# Levels.net
KiCad netlist of a schematic drawn in Altium Designer
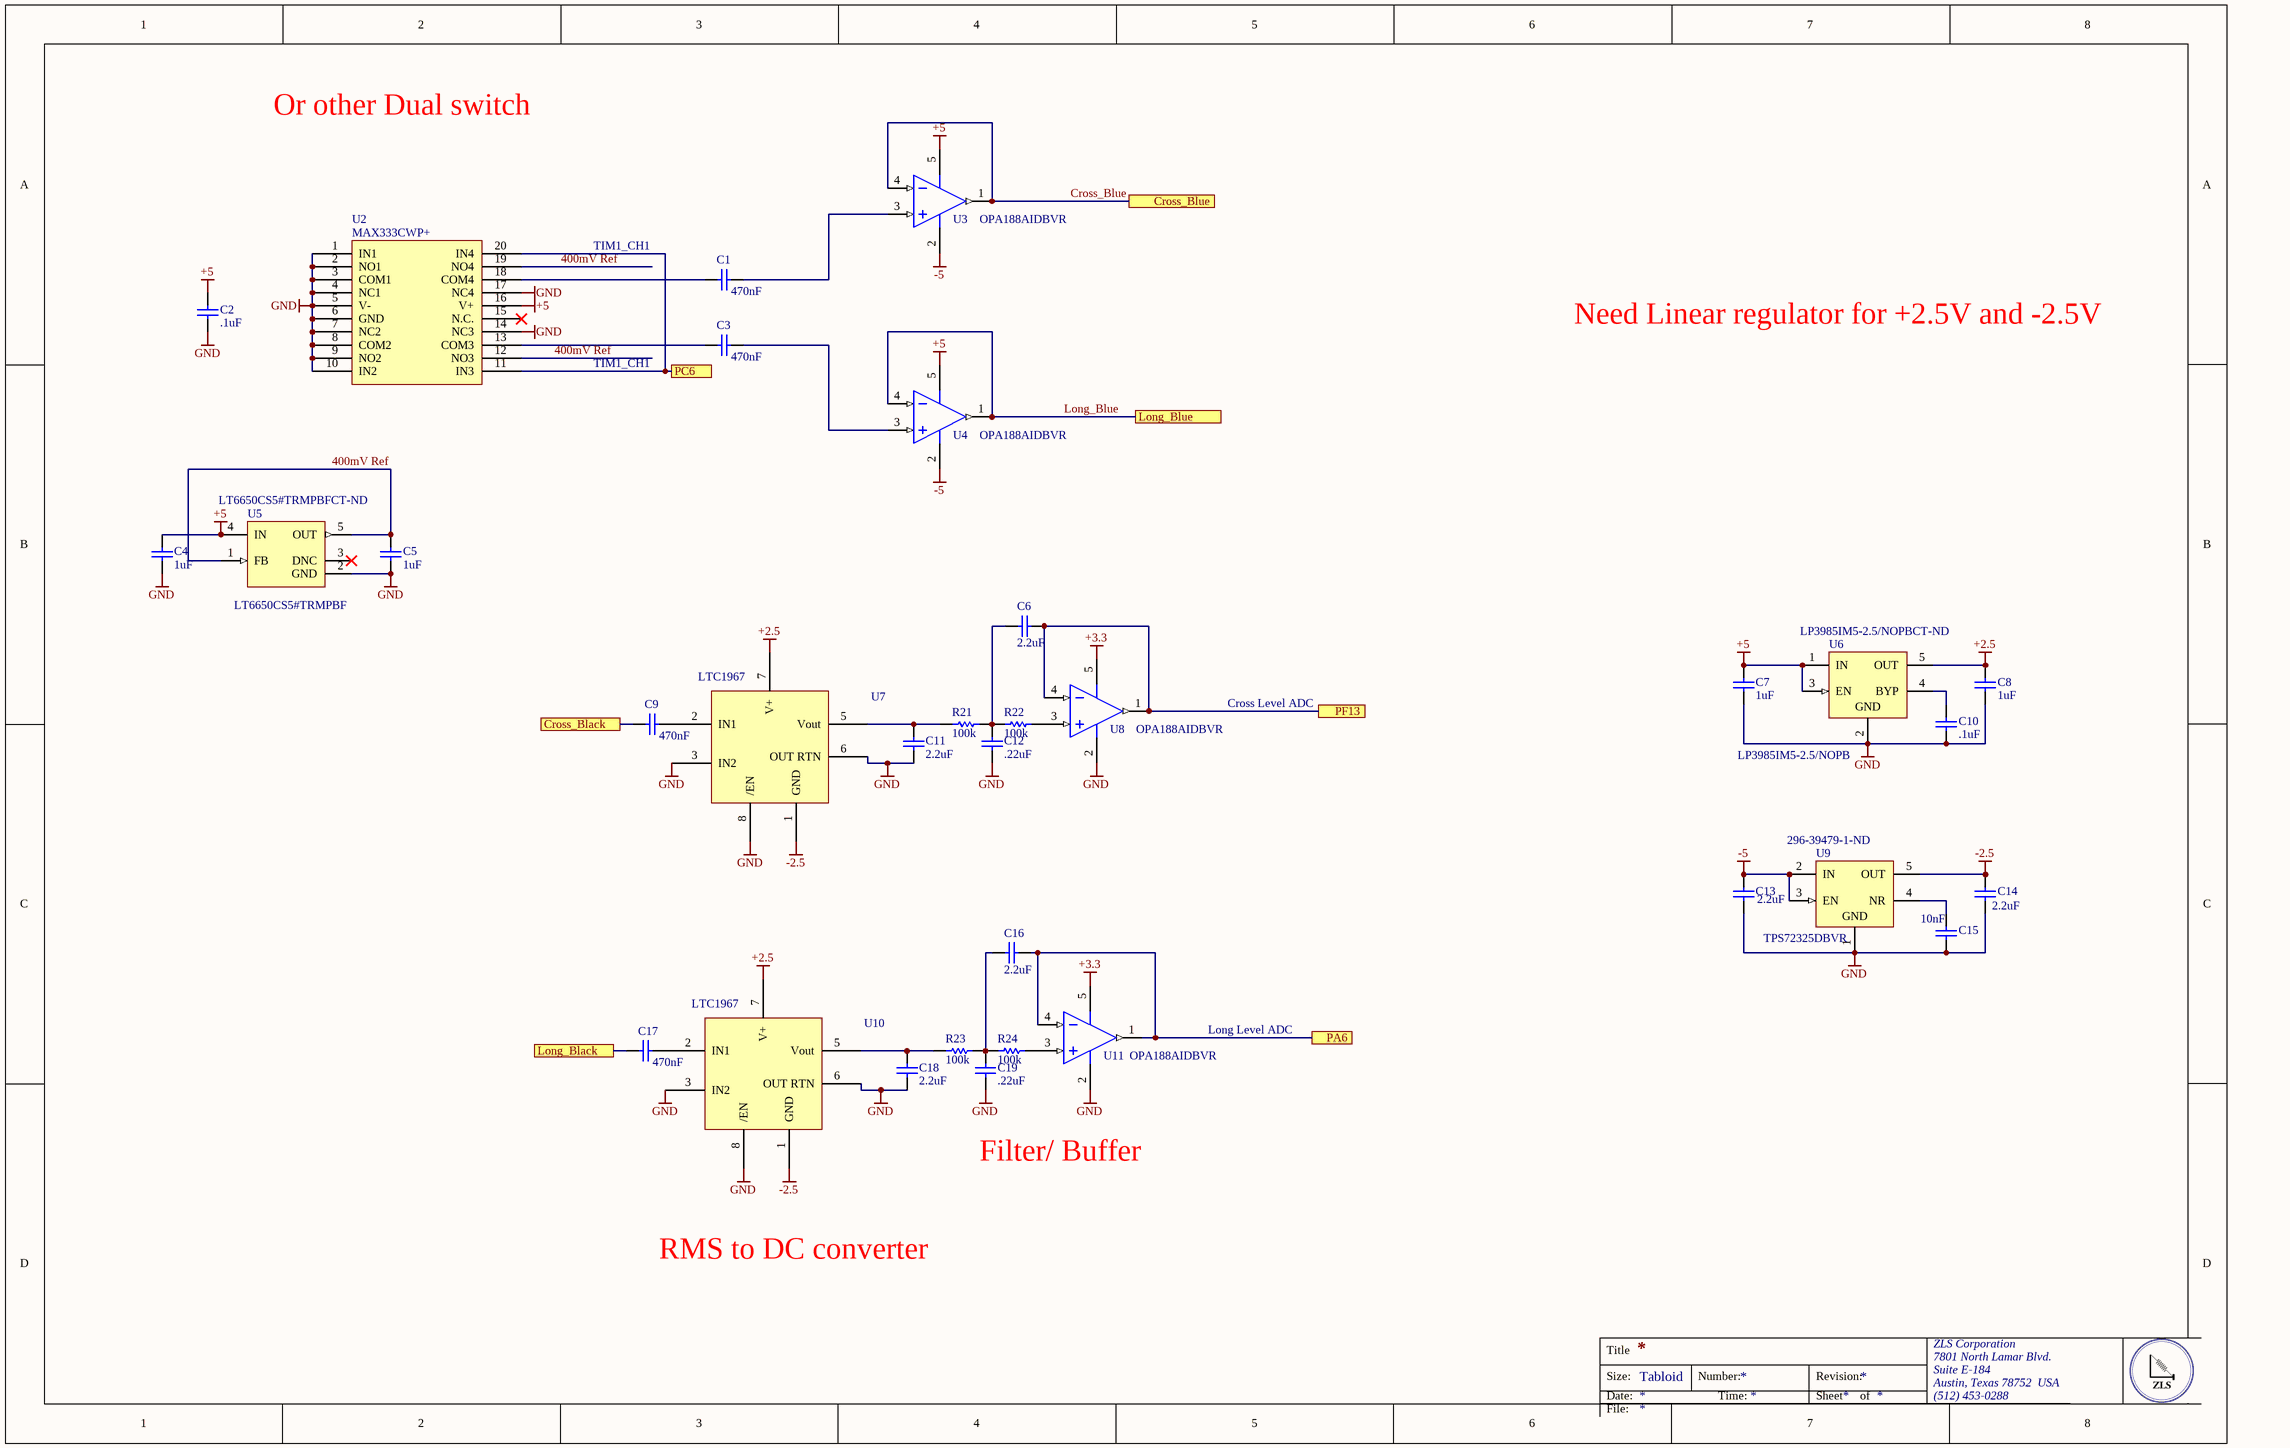
[diagram p0: Levels.SchDoc]

(export (version "E")
  (design (tool "Eeschema 10.0.6"))
  (components
    (comp (ref "C1")
      (value "470nF")
      (footprint "CAPC0805(2012)75_L")
      (description "CAP 150pF 16V ±10% 0805 (2012 Metric) Thickness 0.75mm SMD")
      (fields (field (name "TOLERANCE") "Â±10%"))
      (libsource (lib "Altium Content Vault") (part "CMP-1036-02117-1"))
    )
    (comp (ref "C2")
      (value ".1uF")
      (footprint "CAPC0805(2012)75_L")
      (description "CAP 150pF 16V ±10% 0805 (2012 Metric) Thickness 0.75mm SMD")
      (fields (field (name "TOLERANCE") "Â±10%"))
      (libsource (lib "Altium Content Vault") (part "CMP-1036-02117-1"))
    )
    (comp (ref "C3")
      (value "470nF")
      (footprint "CAPC0805(2012)75_L")
      (description "CAP 150pF 16V ±10% 0805 (2012 Metric) Thickness 0.75mm SMD")
      (fields (field (name "TOLERANCE") "Â±10%"))
      (libsource (lib "Altium Content Vault") (part "CMP-1036-02117-1"))
    )
    (comp (ref "C4")
      (value "08053C105JAT2A")
      (footprint "CAPC0805(2012)145_N")
      (description "1µF ±5% 25V Ceramic Capacitor X7R 0805 (2012 Metric)")
      (fields
        (field (name "TOLERANCE") "Â±5%")
        (field (name "MANUFACTURER") "Kyocera AVX")
        (field (name "CAPACITANCE") "1uF")
      )
      (libsource (lib "Altium Content Vault") (part "CAP"))
    )
    (comp (ref "C5")
      (value "08053C105JAT2A")
      (footprint "CAPC0805(2012)145_N")
      (description "1µF ±5% 25V Ceramic Capacitor X7R 0805 (2012 Metric)")
      (fields
        (field (name "TOLERANCE") "Â±5%")
        (field (name "MANUFACTURER") "Kyocera AVX")
        (field (name "CAPACITANCE") "1uF")
      )
      (libsource (lib "Altium Content Vault") (part "CAP"))
    )
    (comp (ref "C6")
      (value "2.2uF")
      (footprint "CAPC0805(2012)75_L")
      (description "CAP 150pF 16V ±10% 0805 (2012 Metric) Thickness 0.75mm SMD")
      (fields (field (name "TOLERANCE") "Â±10%"))
      (libsource (lib "Altium Content Vault") (part "CMP-1036-02117-1"))
    )
    (comp (ref "C7")
      (value "08053C105JAT2A")
      (footprint "CAPC0805(2012)145_N")
      (description "1µF ±5% 25V Ceramic Capacitor X7R 0805 (2012 Metric)")
      (fields
        (field (name "TOLERANCE") "Â±5%")
        (field (name "MANUFACTURER") "Kyocera AVX")
        (field (name "CAPACITANCE") "1uF")
      )
      (libsource (lib "Altium Content Vault") (part "CAP"))
    )
    (comp (ref "C8")
      (value "08053C105JAT2A")
      (footprint "CAPC0805(2012)145_N")
      (description "1µF ±5% 25V Ceramic Capacitor X7R 0805 (2012 Metric)")
      (fields
        (field (name "TOLERANCE") "Â±5%")
        (field (name "MANUFACTURER") "Kyocera AVX")
        (field (name "CAPACITANCE") "1uF")
      )
      (libsource (lib "Altium Content Vault") (part "CAP"))
    )
    (comp (ref "C9")
      (value "470nF")
      (footprint "CAPC0805(2012)75_L")
      (description "CAP 150pF 16V ±10% 0805 (2012 Metric) Thickness 0.75mm SMD")
      (fields (field (name "TOLERANCE") "Â±10%"))
      (libsource (lib "Altium Content Vault") (part "CMP-1036-02117-1"))
    )
    (comp (ref "C10")
      (value ".1uF")
      (footprint "CAPC0805(2012)75_L")
      (description "0.1µF ±10% 25V Ceramic Capacitor X7R 0805 (2012 Metric)")
      (fields
        (field (name "MANUFACTURER") "Vishay")
        (field (name "MANUFACTURER PART NUMBER") "VJ0805Y104KXXCW1BC")
      )
      (libsource (lib "Altium Content Vault") (part "CMP-1036-02117-1"))
    )
    (comp (ref "C11")
      (value "2.2uF")
      (footprint "CAPC0805(2012)75_L")
      (description "CAP 150pF 16V ±10% 0805 (2012 Metric) Thickness 0.75mm SMD")
      (fields (field (name "TOLERANCE") "Â±10%"))
      (libsource (lib "Altium Content Vault") (part "CMP-1036-02117-1"))
    )
    (comp (ref "C12")
      (value ".22uF")
      (footprint "CAPC0805(2012)75_L")
      (description "CAP 150pF 16V ±10% 0805 (2012 Metric) Thickness 0.75mm SMD")
      (fields (field (name "TOLERANCE") "Â±10%"))
      (libsource (lib "Altium Content Vault") (part "CMP-1036-02117-1"))
    )
    (comp (ref "C13")
      (value "GRM21BR71A225KA01L")
      (footprint "CAPC2013X135X50ML10T20")
      (description "2.2µF ±10% 10V Ceramic Capacitor X7R 0805 (2012 Metric)")
      (fields
        (field (name "MANUFACTURER") "Murata")
        (field (name "CAPACITANCE") "2.2uF")
        (field (name "TOLERANCE") "10%")
      )
      (libsource (lib "Altium Content Vault") (part "CAP"))
    )
    (comp (ref "C14")
      (value "GRM21BR71A225KA01L")
      (footprint "CAPC2013X135X50ML10T20")
      (description "2.2µF ±10% 10V Ceramic Capacitor X7R 0805 (2012 Metric)")
      (fields
        (field (name "MANUFACTURER") "Murata")
        (field (name "CAPACITANCE") "2.2uF")
        (field (name "TOLERANCE") "10%")
      )
      (libsource (lib "Altium Content Vault") (part "CAP"))
    )
    (comp (ref "C15")
      (value "0805ZC103KAT2A")
      (footprint "CAPC2013X140X50NL20T25")
      (description "10000pF ±10% 10V Ceramic Capacitor X7R 0805 (2012 Metric)")
      (fields
        (field (name "MANUFACTURER") "AVX Interconnect / Elco")
        (field (name "CAPACITANCE") "10nF")
        (field (name "TOLERANCE") "10%")
      )
      (libsource (lib "Altium Content Vault") (part "CAP"))
    )
    (comp (ref "C16")
      (value "2.2uF")
      (footprint "CAPC0805(2012)75_L")
      (description "CAP 150pF 16V ±10% 0805 (2012 Metric) Thickness 0.75mm SMD")
      (fields (field (name "TOLERANCE") "Â±10%"))
      (libsource (lib "Altium Content Vault") (part "CMP-1036-02117-1"))
    )
    (comp (ref "C17")
      (value "470nF")
      (footprint "CAPC0805(2012)75_L")
      (description "CAP 150pF 16V ±10% 0805 (2012 Metric) Thickness 0.75mm SMD")
      (fields (field (name "TOLERANCE") "Â±10%"))
      (libsource (lib "Altium Content Vault") (part "CMP-1036-02117-1"))
    )
    (comp (ref "C18")
      (value "2.2uF")
      (footprint "CAPC0805(2012)75_L")
      (description "CAP 150pF 16V ±10% 0805 (2012 Metric) Thickness 0.75mm SMD")
      (fields (field (name "TOLERANCE") "Â±10%"))
      (libsource (lib "Altium Content Vault") (part "CMP-1036-02117-1"))
    )
    (comp (ref "C19")
      (value ".22uF")
      (footprint "CAPC0805(2012)75_L")
      (description "CAP 150pF 16V ±10% 0805 (2012 Metric) Thickness 0.75mm SMD")
      (fields (field (name "TOLERANCE") "Â±10%"))
      (libsource (lib "Altium Content Vault") (part "CMP-1036-02117-1"))
    )
    (comp (ref "R21")
      (value "100k")
      (footprint "RESC0805(2012)_L")
      (description "2R55 0.125W 1% 0805 (2012 Metric)  SMD")
      (fields (field (name "TOLERANCE") "1 %") (field (name "POWER") "0.125 W"))
      (libsource (lib "Altium Content Vault") (part "CMP-1013-00215-1"))
    )
    (comp (ref "R22")
      (value "100k")
      (footprint "RESC0805(2012)_L")
      (description "2R55 0.125W 1% 0805 (2012 Metric)  SMD")
      (fields (field (name "TOLERANCE") "1 %") (field (name "POWER") "0.125 W"))
      (libsource (lib "Altium Content Vault") (part "CMP-1013-00215-1"))
    )
    (comp (ref "R23")
      (value "100k")
      (footprint "RESC0805(2012)_L")
      (description "2R55 0.125W 1% 0805 (2012 Metric)  SMD")
      (fields (field (name "TOLERANCE") "1 %") (field (name "POWER") "0.125 W"))
      (libsource (lib "Altium Content Vault") (part "CMP-1013-00215-1"))
    )
    (comp (ref "R24")
      (value "100k")
      (footprint "RESC0805(2012)_L")
      (description "2R55 0.125W 1% 0805 (2012 Metric)  SMD")
      (fields (field (name "TOLERANCE") "1 %") (field (name "POWER") "0.125 W"))
      (libsource (lib "Altium Content Vault") (part "CMP-1013-00215-1"))
    )
    (comp (ref "U2")
      (value "MAX333CWP+")
      (footprint "TSOP65P640X90-20N")
      (description "IC SWITCH QUAD SPDT 20TSSOP")
      (fields (field (name "MANUFACTURER") "Maxim") (field (name "MANUFACTURER PART NUMBER") "MAX333AEUP+"))
      (libsource (lib "ZLS_Schematic_lib") (part "MAX333CWP+"))
    )
    (comp (ref "U3")
      (value "OPA188AIDBVR")
      (footprint "DBV0005A_M")
      (fields (field (name "MANUFACTURER") "Texas Instruments"))
      (libsource (lib "Altium Content Vault") (part "CMP-0809-00005-2"))
    )
    (comp (ref "U4")
      (value "OPA188AIDBVR")
      (footprint "DBV0005A_M")
      (fields (field (name "MANUFACTURER") "Texas Instruments"))
      (libsource (lib "Altium Content Vault") (part "CMP-0809-00005-2"))
    )
    (comp (ref "U5")
      (value "LT6650CS5#TRMPBF")
      (footprint "LT-S5-5-TSOT-23_N")
      (fields
        (field (name "SUPPLIER PART NUMBER 1") "LT6650CS5#TRMPBFCT-ND")
        (field (name "MANUFACTURER") "Analog Devices / Linear Technology")
        (field (name "TOLERANCE") "0.75%")
      )
      (libsource (lib "Altium Content Vault") (part "LT-LT6650-S5-5"))
    )
    (comp (ref "U6")
      (value "LP3985IM5-2.5/NOPB")
      (footprint "DBV0005A_M")
      (description "Micropower, 150mA Low-Noise Ultra Low-Dropout CMOS Voltage Regulator, 5-pin SOT-23, Pb-Free")
      (fields
        (field (name "MANUFACTURER") "Texas Instruments")
        (field (name "SUPPLIER PART NUMBER 1") "LP3985IM5-2.5/NOPBCT-ND")
      )
      (libsource (lib "Altium Content Vault") (part "PM-REG-LP3985-SOT5"))
    )
    (comp (ref "U7")
      (value "LTC1967")
      (footprint "LTC1967")
      (description "IC CONVERTER RMS-DC PREC 9MSOP")
      (libsource (lib "ZLS_Schematic_lib") (part "LTC1967"))
    )
    (comp (ref "U8")
      (value "OPA188AIDBVR")
      (footprint "DBV0005A_M")
      (fields (field (name "MANUFACTURER") "Texas Instruments"))
      (libsource (lib "Altium Content Vault") (part "CMP-0809-00005-2"))
    )
    (comp (ref "U9")
      (value "TPS72325DBVR")
      (footprint "DBV0005A_N")
      (fields
        (field (name "MANUFACTURER") "Texas Instruments")
        (field (name "SUPPLIER PART NUMBER 1") "296-39479-1-ND")
      )
      (libsource (lib "Altium Content Vault") (part "TI-TPS72325-DBV5"))
    )
    (comp (ref "U10")
      (value "LTC1967")
      (footprint "LTC1967")
      (description "IC CONVERTER RMS-DC PREC 9MSOP")
      (libsource (lib "ZLS_Schematic_lib") (part "LTC1967"))
    )
    (comp (ref "U11")
      (value "OPA188AIDBVR")
      (footprint "DBV0005A_M")
      (fields (field (name "MANUFACTURER") "Texas Instruments"))
      (libsource (lib "Altium Content Vault") (part "CMP-0809-00005-2"))
    )
  )
  (nets
    (net (code "1") (name "+2.5") (class "Default")
      (node (ref "C8") (pin "2") (pinfunction "2_2") (pintype "passive"))
      (node (ref "U10") (pin "7") (pinfunction "V+_7") (pintype "passive"))
      (node (ref "U6") (pin "5") (pinfunction "OUT_5") (pintype "power_in"))
      (node (ref "U7") (pin "7") (pinfunction "V+_7") (pintype "passive"))
    )
    (net (code "2") (name "+3.3") (class "Default")
      (node (ref "U11") (pin "5") (pinfunction "V+_5") (pintype "power_in"))
      (node (ref "U8") (pin "5") (pinfunction "V+_5") (pintype "power_in"))
    )
    (net (code "3") (name "+5") (class "Default")
      (node (ref "C2") (pin "2") (pinfunction "2_2") (pintype "passive"))
      (node (ref "C4") (pin "2") (pinfunction "2_2") (pintype "passive"))
      (node (ref "C7") (pin "2") (pinfunction "2_2") (pintype "passive"))
      (node (ref "U2") (pin "16") (pinfunction "V+_16") (pintype "power_in"))
      (node (ref "U3") (pin "5") (pinfunction "V+_5") (pintype "power_in"))
      (node (ref "U4") (pin "5") (pinfunction "V+_5") (pintype "power_in"))
      (node (ref "U5") (pin "4") (pinfunction "IN_4") (pintype "power_in"))
      (node (ref "U6") (pin "1") (pinfunction "IN_1") (pintype "power_in"))
      (node (ref "U6") (pin "3") (pinfunction "EN_3") (pintype "input"))
    )
    (net (code "4") (name "-2.5") (class "Default")
      (node (ref "C14") (pin "2") (pinfunction "2_2") (pintype "passive"))
      (node (ref "U10") (pin "1") (pinfunction "GND_1") (pintype "passive"))
      (node (ref "U7") (pin "1") (pinfunction "GND_1") (pintype "passive"))
      (node (ref "U9") (pin "5") (pinfunction "OUT_5") (pintype "power_in"))
    )
    (net (code "5") (name "-5") (class "Default")
      (node (ref "C13") (pin "2") (pinfunction "2_2") (pintype "passive"))
      (node (ref "U3") (pin "2") (pinfunction "V-_2") (pintype "power_in"))
      (node (ref "U4") (pin "2") (pinfunction "V-_2") (pintype "power_in"))
      (node (ref "U9") (pin "2") (pinfunction "IN_2") (pintype "power_in"))
      (node (ref "U9") (pin "3") (pinfunction "EN_3") (pintype "input"))
    )
    (net (code "6") (name "/400mV Ref") (class "Default")
      (node (ref "C5") (pin "2") (pinfunction "2_2") (pintype "passive"))
      (node (ref "U2") (pin "12") (pinfunction "NO3_12") (pintype "passive"))
      (node (ref "U2") (pin "19") (pinfunction "NO4_19") (pintype "passive"))
      (node (ref "U5") (pin "1") (pinfunction "FB_1") (pintype "input"))
      (node (ref "U5") (pin "5") (pinfunction "OUT_5") (pintype "output"))
    )
    (net (code "7") (name "/Cross_Black") (class "Default")
      (node (ref "C9") (pin "1") (pinfunction "1_1") (pintype "passive"))
    )
    (net (code "8") (name "/Cross_Blue") (class "Default")
      (node (ref "U3") (pin "1") (pinfunction "OUT_1") (pintype "output"))
      (node (ref "U3") (pin "4") (pinfunction "IN-_4") (pintype "input"))
    )
    (net (code "9") (name "/Long_Black") (class "Default")
      (node (ref "C17") (pin "1") (pinfunction "1_1") (pintype "passive"))
    )
    (net (code "10") (name "/Long_Blue") (class "Default")
      (node (ref "U4") (pin "1") (pinfunction "OUT_1") (pintype "output"))
      (node (ref "U4") (pin "4") (pinfunction "IN-_4") (pintype "input"))
    )
    (net (code "11") (name "/PA6") (class "Default")
      (node (ref "C16") (pin "1") (pinfunction "1_1") (pintype "passive"))
      (node (ref "U11") (pin "1") (pinfunction "OUT_1") (pintype "output"))
      (node (ref "U11") (pin "4") (pinfunction "IN-_4") (pintype "input"))
    )
    (net (code "12") (name "/PC6") (class "Default")
      (node (ref "U2") (pin "11") (pinfunction "IN3_11") (pintype "passive"))
      (node (ref "U2") (pin "20") (pinfunction "IN4_20") (pintype "passive"))
    )
    (net (code "13") (name "/PF13") (class "Default")
      (node (ref "C6") (pin "1") (pinfunction "1_1") (pintype "passive"))
      (node (ref "U8") (pin "1") (pinfunction "OUT_1") (pintype "output"))
      (node (ref "U8") (pin "4") (pinfunction "IN-_4") (pintype "input"))
    )
    (net (code "14") (name "GND") (class "Default")
      (node (ref "C10") (pin "1") (pinfunction "1_1") (pintype "passive"))
      (node (ref "C11") (pin "1") (pinfunction "1_1") (pintype "passive"))
      (node (ref "C12") (pin "1") (pinfunction "1_1") (pintype "passive"))
      (node (ref "C13") (pin "1") (pinfunction "1_1") (pintype "passive"))
      (node (ref "C14") (pin "1") (pinfunction "1_1") (pintype "passive"))
      (node (ref "C15") (pin "1") (pinfunction "1_1") (pintype "passive"))
      (node (ref "C18") (pin "1") (pinfunction "1_1") (pintype "passive"))
      (node (ref "C19") (pin "1") (pinfunction "1_1") (pintype "passive"))
      (node (ref "C2") (pin "1") (pinfunction "1_1") (pintype "passive"))
      (node (ref "C4") (pin "1") (pinfunction "1_1") (pintype "passive"))
      (node (ref "C5") (pin "1") (pinfunction "1_1") (pintype "passive"))
      (node (ref "C7") (pin "1") (pinfunction "1_1") (pintype "passive"))
      (node (ref "C8") (pin "1") (pinfunction "1_1") (pintype "passive"))
      (node (ref "U10") (pin "3") (pinfunction "IN2_3") (pintype "passive"))
      (node (ref "U10") (pin "6") (pinfunction "OUT_RTN_6") (pintype "passive"))
      (node (ref "U10") (pin "8") (pinfunction "/EN_8") (pintype "passive"))
      (node (ref "U11") (pin "2") (pinfunction "V-_2") (pintype "power_in"))
      (node (ref "U2") (pin "1") (pinfunction "IN1_1") (pintype "passive"))
      (node (ref "U2") (pin "10") (pinfunction "IN2_10") (pintype "passive"))
      (node (ref "U2") (pin "14") (pinfunction "NC3_14") (pintype "passive"))
      (node (ref "U2") (pin "17") (pinfunction "NC4_17") (pintype "passive"))
      (node (ref "U2") (pin "2") (pinfunction "NO1_2") (pintype "passive"))
      (node (ref "U2") (pin "3") (pinfunction "COM1_3") (pintype "passive"))
      (node (ref "U2") (pin "4") (pinfunction "NC1_4") (pintype "passive"))
      (node (ref "U2") (pin "5") (pinfunction "V-_5") (pintype "power_in"))
      (node (ref "U2") (pin "6") (pinfunction "GND_6") (pintype "passive"))
      (node (ref "U2") (pin "7") (pinfunction "NC2_7") (pintype "passive"))
      (node (ref "U2") (pin "8") (pinfunction "COM2_8") (pintype "passive"))
      (node (ref "U2") (pin "9") (pinfunction "NO2_9") (pintype "passive"))
      (node (ref "U5") (pin "2") (pinfunction "GND_2") (pintype "power_in"))
      (node (ref "U6") (pin "2") (pinfunction "GND_2") (pintype "power_in"))
      (node (ref "U7") (pin "3") (pinfunction "IN2_3") (pintype "passive"))
      (node (ref "U7") (pin "6") (pinfunction "OUT_RTN_6") (pintype "passive"))
      (node (ref "U7") (pin "8") (pinfunction "/EN_8") (pintype "passive"))
      (node (ref "U8") (pin "2") (pinfunction "V-_2") (pintype "power_in"))
      (node (ref "U9") (pin "1") (pinfunction "GND_1") (pintype "power_in"))
    )
    (net (code "15") (name "Net-(C12-Pad2)") (class "Default")
      (node (ref "C12") (pin "2") (pinfunction "2_2") (pintype "passive"))
      (node (ref "C6") (pin "2") (pinfunction "2_2") (pintype "passive"))
      (node (ref "R21") (pin "1") (pinfunction "1_1") (pintype "passive"))
      (node (ref "R22") (pin "2") (pinfunction "2_2") (pintype "passive"))
    )
    (net (code "16") (name "Net-(C16-Pad2)") (class "Default")
      (node (ref "C16") (pin "2") (pinfunction "2_2") (pintype "passive"))
      (node (ref "C19") (pin "2") (pinfunction "2_2") (pintype "passive"))
      (node (ref "R23") (pin "1") (pinfunction "1_1") (pintype "passive"))
      (node (ref "R24") (pin "2") (pinfunction "2_2") (pintype "passive"))
    )
    (net (code "17") (name "Net-(U2-COM3)") (class "Default")
      (node (ref "C3") (pin "1") (pinfunction "1_1") (pintype "passive"))
      (node (ref "U2") (pin "13") (pinfunction "COM3_13") (pintype "passive"))
    )
    (net (code "18") (name "Net-(U2-COM4)") (class "Default")
      (node (ref "C1") (pin "1") (pinfunction "1_1") (pintype "passive"))
      (node (ref "U2") (pin "18") (pinfunction "COM4_18") (pintype "passive"))
    )
    (net (code "19") (name "Net-(U3-IN+)") (class "Default")
      (node (ref "C1") (pin "2") (pinfunction "2_2") (pintype "passive"))
      (node (ref "U3") (pin "3") (pinfunction "IN+_3") (pintype "input"))
    )
    (net (code "20") (name "Net-(U4-IN+)") (class "Default")
      (node (ref "C3") (pin "2") (pinfunction "2_2") (pintype "passive"))
      (node (ref "U4") (pin "3") (pinfunction "IN+_3") (pintype "input"))
    )
    (net (code "21") (name "Net-(U6-BYP)") (class "Default")
      (node (ref "C10") (pin "2") (pinfunction "2_2") (pintype "passive"))
      (node (ref "U6") (pin "4") (pinfunction "BYP_4") (pintype "passive"))
    )
    (net (code "22") (name "Net-(U7-IN1)") (class "Default")
      (node (ref "C9") (pin "2") (pinfunction "2_2") (pintype "passive"))
      (node (ref "U7") (pin "2") (pinfunction "IN1_2") (pintype "passive"))
    )
    (net (code "23") (name "Net-(U7-Vout)") (class "Default")
      (node (ref "C11") (pin "2") (pinfunction "2_2") (pintype "passive"))
      (node (ref "R21") (pin "2") (pinfunction "2_2") (pintype "passive"))
      (node (ref "U7") (pin "5") (pinfunction "Vout_5") (pintype "passive"))
    )
    (net (code "24") (name "Net-(U8-IN+)") (class "Default")
      (node (ref "R22") (pin "1") (pinfunction "1_1") (pintype "passive"))
      (node (ref "U8") (pin "3") (pinfunction "IN+_3") (pintype "input"))
    )
    (net (code "25") (name "Net-(U9-NR)") (class "Default")
      (node (ref "C15") (pin "2") (pinfunction "2_2") (pintype "passive"))
      (node (ref "U9") (pin "4") (pinfunction "NR_4") (pintype "passive"))
    )
    (net (code "26") (name "Net-(U10-IN1)") (class "Default")
      (node (ref "C17") (pin "2") (pinfunction "2_2") (pintype "passive"))
      (node (ref "U10") (pin "2") (pinfunction "IN1_2") (pintype "passive"))
    )
    (net (code "27") (name "Net-(U10-Vout)") (class "Default")
      (node (ref "C18") (pin "2") (pinfunction "2_2") (pintype "passive"))
      (node (ref "R23") (pin "2") (pinfunction "2_2") (pintype "passive"))
      (node (ref "U10") (pin "5") (pinfunction "Vout_5") (pintype "passive"))
    )
    (net (code "28") (name "Net-(U11-IN+)") (class "Default")
      (node (ref "R24") (pin "1") (pinfunction "1_1") (pintype "passive"))
      (node (ref "U11") (pin "3") (pinfunction "IN+_3") (pintype "input"))
    )
    (net (code "29") (name "unconnected-(U2-N.C.-Pad15)") (class "Default")
      (node (ref "U2") (pin "15") (pinfunction "N.C._15") (pintype "passive+no_connect"))
    )
    (net (code "30") (name "unconnected-(U5-DNC-Pad3)") (class "Default")
      (node (ref "U5") (pin "3") (pinfunction "DNC_3") (pintype "passive+no_connect"))
    )
    (net (code "31") (name "unconnected-(U7-NC-Pad4)") (class "Default")
      (node (ref "U7") (pin "4") (pinfunction "NC_4") (pintype "passive"))
    )
    (net (code "32") (name "unconnected-(U10-NC-Pad4)") (class "Default")
      (node (ref "U10") (pin "4") (pinfunction "NC_4") (pintype "passive"))
    )
  )
)
